# B293A_Monitor.net
KiCad netlist of a schematic drawn in Altium Designer
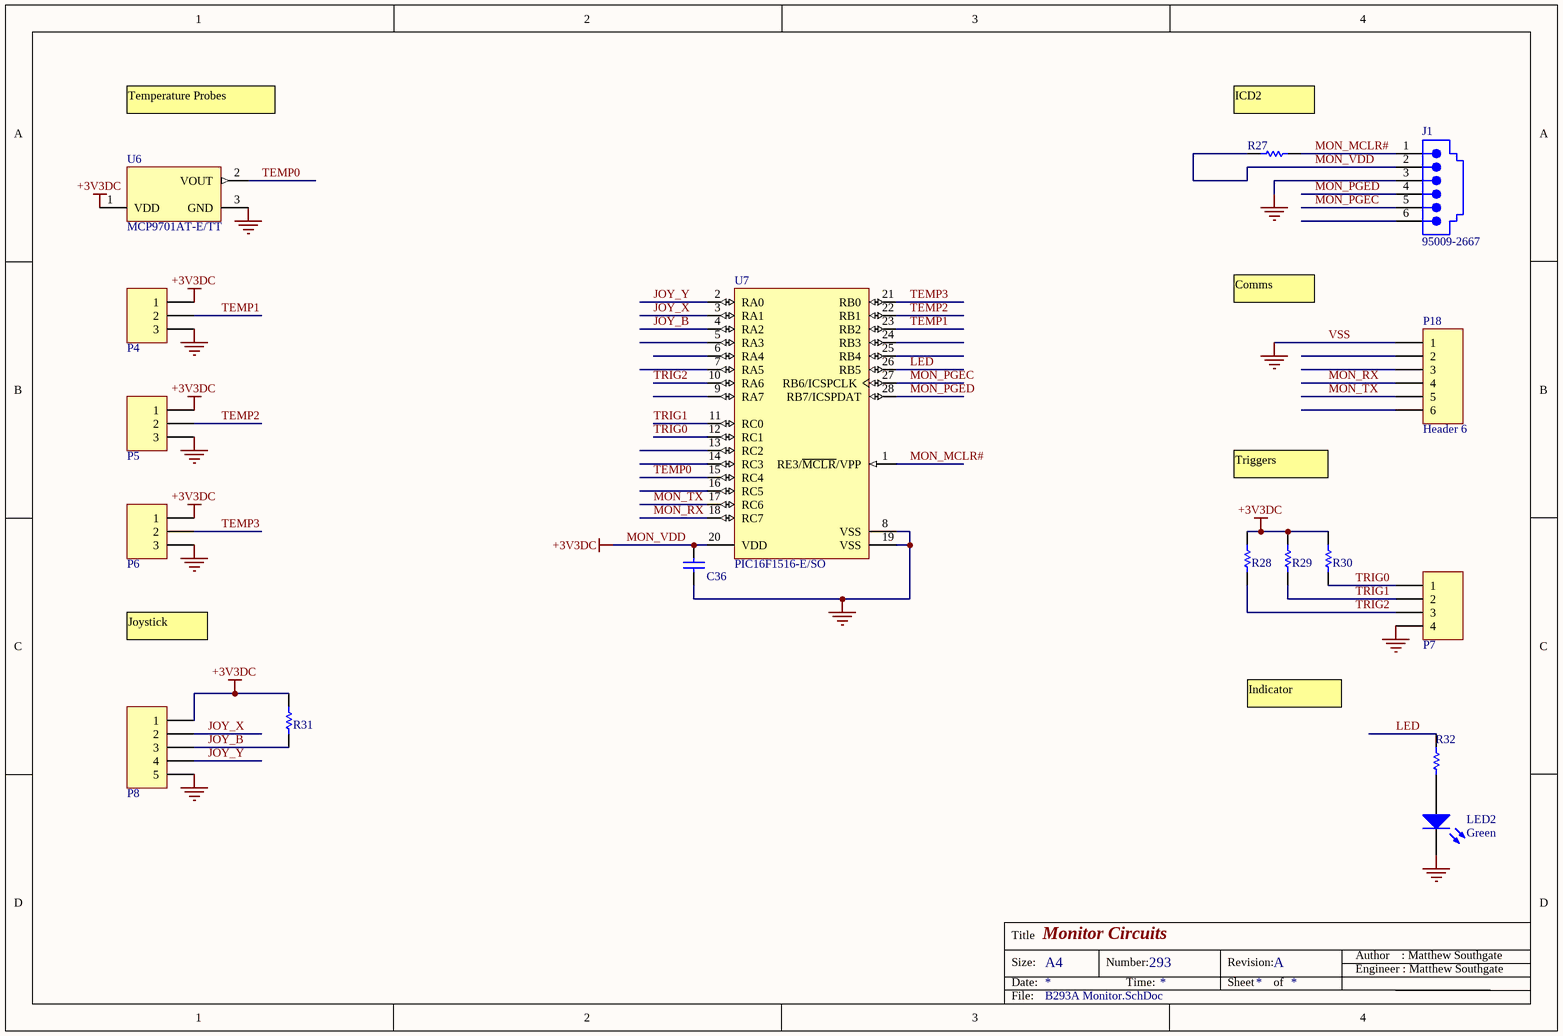
[diagram p0: B293A Monitor.SchDoc]

(export (version "E")
  (design (tool "Eeschema 10.0.6"))
  (components
    (comp (ref "C36")
      (value "CAP 120nF 50V 0805(2012)")
      (footprint "CAPC0805(2012)145_N")
      (description "CAP 120nF 50V ±20% 0805 (2012 Metric) Thickness 1.45mm SMD")
      (fields (field (name "TOLERANCE") "±20%"))
      (libsource (lib "Altium Content Vault") (part "CAP"))
    )
    (comp (ref "J1")
      (value "95009-2667")
      (footprint "95009-2667")
      (description "MOLEX - 95009-2667 - JACK PLUG")
      (fields (field (name "MANUFACTURER") "MOLEX") (field (name "PUBLISHER") "Altium Limited"))
      (libsource (lib "Matt SCH Library") (part "95009-2667"))
    )
    (comp (ref "LED2")
      (value "Green")
      (footprint "Matt PCB Library:1206 - LED")
      (description "LED, SMD, 1206, CLR LENS, GREEN")
      (fields
        (field (name "MANUFACTURER PART NUMBER") "KPC-3216SGC")
        (field (name "MANUFACTURER") "KINGBRIGHT")
      )
      (libsource (lib "Matt SCH Library") (part "LED 1206 GREEN"))
    )
    (comp (ref "P4")
      (value "MOLEX SL 3W VERT")
      (footprint "MOLEX SL 3W Vertical with latch")
      (description "MOLEX - 70543-0037 - WIRE-BOARD CONNECTOR HEADER 3POS, 2.54MM")
      (fields (field (name "MANUFACTURER PART NUMBER") "70543-0037"))
      (libsource (lib "Matt SCH Library") (part "MOLEX SL 3W VERT"))
    )
    (comp (ref "P5")
      (value "MOLEX SL 3W VERT")
      (footprint "MOLEX SL 3W Vertical with latch")
      (description "MOLEX - 70543-0037 - WIRE-BOARD CONNECTOR HEADER 3POS, 2.54MM")
      (fields (field (name "MANUFACTURER PART NUMBER") "70543-0037"))
      (libsource (lib "Matt SCH Library") (part "MOLEX SL 3W VERT"))
    )
    (comp (ref "P6")
      (value "MOLEX SL 3W VERT")
      (footprint "MOLEX SL 3W Vertical with latch")
      (description "MOLEX - 70543-0037 - WIRE-BOARD CONNECTOR HEADER 3POS, 2.54MM")
      (fields (field (name "MANUFACTURER PART NUMBER") "70543-0037"))
      (libsource (lib "Matt SCH Library") (part "MOLEX SL 3W VERT"))
    )
    (comp (ref "P7")
      (value "MOLEX SL 4W VERT")
      (footprint "MOLEX SL 4W Vertical with latch")
      (description "MOLEX - 70543-0108 - CONNECTOR, HEADER, 4POS, 1ROW, 2.54MM")
      (fields (field (name "MANUFACTURER PART NUMBER") "70543-0108"))
      (libsource (lib "Matt SCH Library") (part "MOLEX SL 4W VERT"))
    )
    (comp (ref "P8")
      (value "MOLEX SL 5W VERT")
      (footprint "MOLEX SL 5W Vertical with latch")
      (description "MOLEX - 70543-0004 - CONNECTOR, HEADER, 5POS, 1ROW, 2.54MM")
      (fields (field (name "MANUFACTURER PART NUMBER") "70543-0004"))
      (libsource (lib "Matt SCH Library") (part "MOLEX SL 5W VERT"))
    )
    (comp (ref "P18")
      (value "Header 6")
      (footprint "HDR1X6")
      (description "Header, 6-Pin")
      (fields (field (name "PUBLISHER") "Altium Limited"))
      (libsource (lib "Miscellaneous Connectors") (part "Header 6"))
    )
    (comp (ref "R27")
      (value "10K 5% 0805(2012)")
      (footprint "RESC0805(2012)_L")
      (description "10K 0.125W 5% 0805 (2012 Metric)  SMD")
      (fields (field (name "POWER") "0.125 W") (field (name "TOLERANCE") "5 %"))
      (libsource (lib "Altium Content Vault") (part "RES"))
    )
    (comp (ref "R28")
      (value "10K 5% 0805(2012)")
      (footprint "RESC0805(2012)_L")
      (description "10K 0.125W 5% 0805 (2012 Metric)  SMD")
      (fields (field (name "POWER") "0.125 W") (field (name "TOLERANCE") "5 %"))
      (libsource (lib "Altium Content Vault") (part "RES"))
    )
    (comp (ref "R29")
      (value "10K 5% 0805(2012)")
      (footprint "RESC0805(2012)_L")
      (description "10K 0.125W 5% 0805 (2012 Metric)  SMD")
      (fields (field (name "POWER") "0.125 W") (field (name "TOLERANCE") "5 %"))
      (libsource (lib "Altium Content Vault") (part "RES"))
    )
    (comp (ref "R30")
      (value "10K 5% 0805(2012)")
      (footprint "RESC0805(2012)_L")
      (description "10K 0.125W 5% 0805 (2012 Metric)  SMD")
      (fields (field (name "POWER") "0.125 W") (field (name "TOLERANCE") "5 %"))
      (libsource (lib "Altium Content Vault") (part "RES"))
    )
    (comp (ref "R31")
      (value "10K 5% 0805(2012)")
      (footprint "RESC0805(2012)_L")
      (description "10K 0.125W 5% 0805 (2012 Metric)  SMD")
      (fields (field (name "POWER") "0.125 W") (field (name "TOLERANCE") "5 %"))
      (libsource (lib "Altium Content Vault") (part "RES"))
    )
    (comp (ref "R32")
      (value "1K 5% 0805(2012)")
      (footprint "RESC0805(2012)_N")
      (description "1K 0.125W 5% 0805 (2012 Metric)  SMD")
      (fields (field (name "TOLERANCE") "5 %") (field (name "POWER") "0.125 W"))
      (libsource (lib "Altium Content Vault") (part "RES"))
    )
    (comp (ref "U6")
      (value "MCP9701AT-E/TT")
      (footprint "SOT-23-TT3_M")
      (description "Low-Power Linear Active Thermistor IC, 3-Pin SOT-23, Extended Temperature, Tape and Reel")
      (libsource (lib "Altium Content Vault") (part "CMP-0192-00221-1"))
    )
    (comp (ref "U7")
      (value "PIC16F1516-E/SO")
      (footprint "MCHP-SOIC-SO28_N")
      (fields (field (name "MANUFACTURER") "Microchip"))
      (libsource (lib "Altium Content Vault") (part "MCHP-PIC16XF151XX_178X-28"))
    )
  )
  (nets
    (net (code "1") (name "+3V3DC") (class "Default")
      (node (ref "C36") (pin "1") (pinfunction "1_1") (pintype "passive"))
      (node (ref "J1") (pin "2") (pinfunction "2_2") (pintype "passive"))
      (node (ref "P4") (pin "1") (pinfunction "1_1") (pintype "passive"))
      (node (ref "P5") (pin "1") (pinfunction "1_1") (pintype "passive"))
      (node (ref "P6") (pin "1") (pinfunction "1_1") (pintype "passive"))
      (node (ref "P8") (pin "1") (pinfunction "1_1") (pintype "passive"))
      (node (ref "R27") (pin "1") (pinfunction "1_1") (pintype "passive"))
      (node (ref "R28") (pin "2") (pinfunction "2_2") (pintype "passive"))
      (node (ref "R29") (pin "2") (pinfunction "2_2") (pintype "passive"))
      (node (ref "R30") (pin "2") (pinfunction "2_2") (pintype "passive"))
      (node (ref "R31") (pin "2") (pinfunction "2_2") (pintype "passive"))
      (node (ref "U6") (pin "1") (pinfunction "VDD_1") (pintype "power_in"))
      (node (ref "U7") (pin "20") (pinfunction "VDD_20") (pintype "power_in"))
    )
    (net (code "2") (name "/JOY_B") (class "Default")
      (node (ref "P8") (pin "3") (pinfunction "3_3") (pintype "passive"))
      (node (ref "R31") (pin "1") (pinfunction "1_1") (pintype "passive"))
      (node (ref "U7") (pin "4") (pinfunction "RA2_4") (pintype "bidirectional"))
    )
    (net (code "3") (name "/JOY_X") (class "Default")
      (node (ref "P8") (pin "2") (pinfunction "2_2") (pintype "passive"))
      (node (ref "U7") (pin "3") (pinfunction "RA1_3") (pintype "bidirectional"))
    )
    (net (code "4") (name "/JOY_Y") (class "Default")
      (node (ref "P8") (pin "4") (pinfunction "4_4") (pintype "passive"))
      (node (ref "U7") (pin "2") (pinfunction "RA0_2") (pintype "bidirectional"))
    )
    (net (code "5") (name "/LED") (class "Default")
      (node (ref "R32") (pin "2") (pinfunction "2_2") (pintype "passive"))
      (node (ref "U7") (pin "26") (pinfunction "RB5_26") (pintype "bidirectional"))
    )
    (net (code "6") (name "/MON_MCLR#") (class "Default")
      (node (ref "J1") (pin "1") (pinfunction "1_1") (pintype "passive"))
      (node (ref "R27") (pin "2") (pinfunction "2_2") (pintype "passive"))
      (node (ref "U7") (pin "1") (pinfunction "RE3/~{MCLR}/VPP_1") (pintype "input"))
    )
    (net (code "7") (name "/MON_PGEC") (class "Default")
      (node (ref "J1") (pin "5") (pinfunction "5_5") (pintype "passive"))
      (node (ref "U7") (pin "27") (pinfunction "RB6/ICSPCLK_27") (pintype "bidirectional"))
    )
    (net (code "8") (name "/MON_PGED") (class "Default")
      (node (ref "J1") (pin "4") (pinfunction "4_4") (pintype "passive"))
      (node (ref "U7") (pin "28") (pinfunction "RB7/ICSPDAT_28") (pintype "bidirectional"))
    )
    (net (code "9") (name "/MON_RX") (class "Default")
      (node (ref "P18") (pin "4") (pinfunction "4_4") (pintype "passive"))
      (node (ref "U7") (pin "18") (pinfunction "RC7_18") (pintype "bidirectional"))
    )
    (net (code "10") (name "/MON_TX") (class "Default")
      (node (ref "P18") (pin "5") (pinfunction "5_5") (pintype "passive"))
      (node (ref "U7") (pin "17") (pinfunction "RC6_17") (pintype "bidirectional"))
    )
    (net (code "11") (name "/TEMP0") (class "Default")
      (node (ref "U6") (pin "2") (pinfunction "VOUT_2") (pintype "output"))
      (node (ref "U7") (pin "15") (pinfunction "RC4_15") (pintype "bidirectional"))
    )
    (net (code "12") (name "/TEMP1") (class "Default")
      (node (ref "P4") (pin "2") (pinfunction "2_2") (pintype "passive"))
      (node (ref "U7") (pin "23") (pinfunction "RB2_23") (pintype "bidirectional"))
    )
    (net (code "13") (name "/TEMP2") (class "Default")
      (node (ref "P5") (pin "2") (pinfunction "2_2") (pintype "passive"))
      (node (ref "U7") (pin "22") (pinfunction "RB1_22") (pintype "bidirectional"))
    )
    (net (code "14") (name "/TEMP3") (class "Default")
      (node (ref "P6") (pin "2") (pinfunction "2_2") (pintype "passive"))
      (node (ref "U7") (pin "21") (pinfunction "RB0_21") (pintype "bidirectional"))
    )
    (net (code "15") (name "/TRIG0") (class "Default")
      (node (ref "P7") (pin "1") (pinfunction "1_1") (pintype "passive"))
      (node (ref "R30") (pin "1") (pinfunction "1_1") (pintype "passive"))
      (node (ref "U7") (pin "12") (pinfunction "RC1_12") (pintype "bidirectional"))
    )
    (net (code "16") (name "/TRIG1") (class "Default")
      (node (ref "P7") (pin "2") (pinfunction "2_2") (pintype "passive"))
      (node (ref "R29") (pin "1") (pinfunction "1_1") (pintype "passive"))
      (node (ref "U7") (pin "11") (pinfunction "RC0_11") (pintype "bidirectional"))
    )
    (net (code "17") (name "/TRIG2") (class "Default")
      (node (ref "P7") (pin "3") (pinfunction "3_3") (pintype "passive"))
      (node (ref "R28") (pin "1") (pinfunction "1_1") (pintype "passive"))
      (node (ref "U7") (pin "10") (pinfunction "RA6_10") (pintype "bidirectional"))
    )
    (net (code "18") (name "GND") (class "Default")
      (node (ref "C36") (pin "2") (pinfunction "2_2") (pintype "passive"))
      (node (ref "J1") (pin "3") (pinfunction "3_3") (pintype "passive"))
      (node (ref "LED2") (pin "K") (pinfunction "K_K") (pintype "passive"))
      (node (ref "P18") (pin "1") (pinfunction "1_1") (pintype "passive"))
      (node (ref "P4") (pin "3") (pinfunction "3_3") (pintype "passive"))
      (node (ref "P5") (pin "3") (pinfunction "3_3") (pintype "passive"))
      (node (ref "P6") (pin "3") (pinfunction "3_3") (pintype "passive"))
      (node (ref "P7") (pin "4") (pinfunction "4_4") (pintype "passive"))
      (node (ref "P8") (pin "5") (pinfunction "5_5") (pintype "passive"))
      (node (ref "U6") (pin "3") (pinfunction "GND_3") (pintype "power_in"))
      (node (ref "U7") (pin "19") (pinfunction "VSS_19") (pintype "power_in"))
      (node (ref "U7") (pin "8") (pinfunction "VSS_8") (pintype "power_in"))
    )
    (net (code "19") (name "Net-(LED2-PadA)") (class "Default")
      (node (ref "LED2") (pin "A") (pinfunction "A_A") (pintype "passive"))
      (node (ref "R32") (pin "1") (pinfunction "1_1") (pintype "passive"))
    )
    (net (code "20") (name "unconnected-(J1-Pad6)") (class "Default")
      (node (ref "J1") (pin "6") (pinfunction "6_6") (pintype "passive"))
    )
    (net (code "21") (name "unconnected-(P18-Pad2)") (class "Default")
      (node (ref "P18") (pin "2") (pinfunction "2_2") (pintype "passive"))
    )
    (net (code "22") (name "unconnected-(P18-Pad3)") (class "Default")
      (node (ref "P18") (pin "3") (pinfunction "3_3") (pintype "passive"))
    )
    (net (code "23") (name "unconnected-(P18-Pad6)") (class "Default")
      (node (ref "P18") (pin "6") (pinfunction "6_6") (pintype "passive"))
    )
    (net (code "24") (name "unconnected-(U7-RA3-Pad5)") (class "Default")
      (node (ref "U7") (pin "5") (pinfunction "RA3_5") (pintype "bidirectional"))
    )
    (net (code "25") (name "unconnected-(U7-RA4-Pad6)") (class "Default")
      (node (ref "U7") (pin "6") (pinfunction "RA4_6") (pintype "bidirectional"))
    )
    (net (code "26") (name "unconnected-(U7-RA5-Pad7)") (class "Default")
      (node (ref "U7") (pin "7") (pinfunction "RA5_7") (pintype "bidirectional"))
    )
    (net (code "27") (name "unconnected-(U7-RA7-Pad9)") (class "Default")
      (node (ref "U7") (pin "9") (pinfunction "RA7_9") (pintype "bidirectional"))
    )
    (net (code "28") (name "unconnected-(U7-RB3-Pad24)") (class "Default")
      (node (ref "U7") (pin "24") (pinfunction "RB3_24") (pintype "bidirectional"))
    )
    (net (code "29") (name "unconnected-(U7-RB4-Pad25)") (class "Default")
      (node (ref "U7") (pin "25") (pinfunction "RB4_25") (pintype "bidirectional"))
    )
    (net (code "30") (name "unconnected-(U7-RC2-Pad13)") (class "Default")
      (node (ref "U7") (pin "13") (pinfunction "RC2_13") (pintype "bidirectional"))
    )
    (net (code "31") (name "unconnected-(U7-RC3-Pad14)") (class "Default")
      (node (ref "U7") (pin "14") (pinfunction "RC3_14") (pintype "bidirectional"))
    )
    (net (code "32") (name "unconnected-(U7-RC5-Pad16)") (class "Default")
      (node (ref "U7") (pin "16") (pinfunction "RC5_16") (pintype "bidirectional"))
    )
  )
)
